# Mic_Circuit.net
KiCad netlist of a schematic drawn in Altium Designer
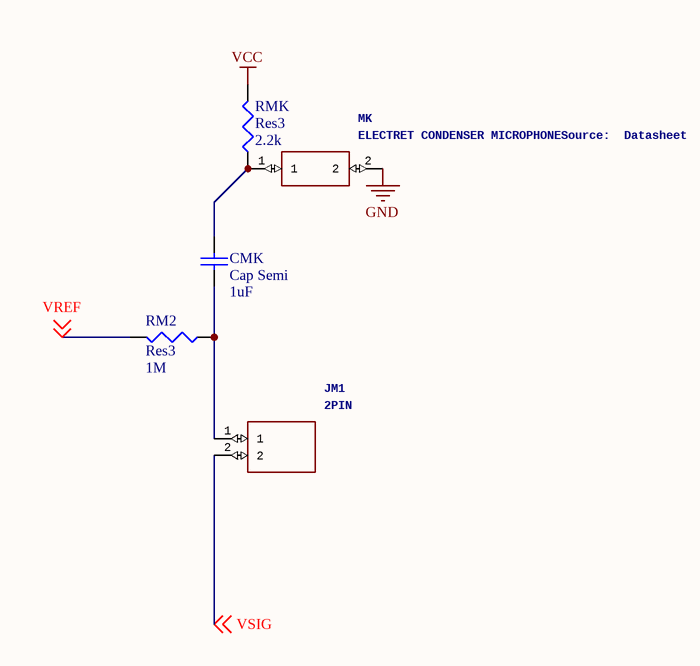
[diagram p0: Mic_Circuit.SchDoc]

(export (version "E")
  (design (tool "Eeschema 10.0.6"))
  (components
    (comp (ref "CMK")
      (value "Cap Semi")
      (footprint "1608[0603]")
      (description "Capacitor (Semiconductor SIM Model)")
      (fields (field (name "ALTIUM_VALUE") "1uF") (field (name "PUBLISHER") "Altium Limited"))
      (libsource (lib "Miscellaneous Devices") (part "Cap Semi"))
    )
    (comp (ref "JM1")
      (value "2PIN")
      (footprint "HDRV2W110P0X254_1X2_508X254X85")
      (fields
        (field (name "MANUFACTURER_PART_NUMBER") "61300211121")
        (field (name "RS_PART_NUMBER") "8281581P")
      )
      (libsource (lib "61300211121") (part "61300211121"))
    )
    (comp (ref "MK")
      (value "ELECTRET CONDENSER MICROPHONESource:  Datasheet")
      (footprint "CMA-4544PF-W")
      (fields (field (name "MANUFACTURER_PART_NUMBER") "CMA-4544PF-W"))
      (libsource (lib "CMA-4544PF-W") (part "CMA-4544PF-W"))
    )
    (comp (ref "RM2")
      (value "Res3")
      (footprint "1608[0603]")
      (description "Resistor")
      (fields (field (name "ALTIUM_VALUE") "1M") (field (name "PUBLISHER") "Altium Limited"))
      (libsource (lib "Miscellaneous Devices") (part "Res3"))
    )
    (comp (ref "RMK")
      (value "Res3")
      (footprint "1608[0603]")
      (description "Resistor")
      (fields (field (name "ALTIUM_VALUE") "2.2k") (field (name "PUBLISHER") "Altium Limited"))
      (libsource (lib "Miscellaneous Devices") (part "Res3"))
    )
  )
  (nets
    (net (code "1") (name "GND") (class "Default")
      (node (ref "MK") (pin "2") (pinfunction "2_2") (pintype "bidirectional"))
    )
    (net (code "2") (name "Net-(CMK-Pad1)") (class "Default")
      (node (ref "CMK") (pin "1") (pinfunction "1_1") (pintype "passive"))
      (node (ref "JM1") (pin "1") (pinfunction "1_1") (pintype "bidirectional"))
      (node (ref "RM2") (pin "2") (pinfunction "2_2") (pintype "passive"))
    )
    (net (code "3") (name "Net-(CMK-Pad2)") (class "Default")
      (node (ref "CMK") (pin "2") (pinfunction "2_2") (pintype "passive"))
      (node (ref "MK") (pin "1") (pinfunction "1_1") (pintype "bidirectional"))
      (node (ref "RMK") (pin "2") (pinfunction "2_2") (pintype "passive"))
    )
    (net (code "4") (name "VCC") (class "Default")
      (node (ref "RMK") (pin "1") (pinfunction "1_1") (pintype "passive"))
    )
    (net (code "5") (name "VREF") (class "Default")
      (node (ref "RM2") (pin "1") (pinfunction "1_1") (pintype "passive"))
    )
    (net (code "6") (name "VSIG") (class "Default")
      (node (ref "JM1") (pin "2") (pinfunction "2_2") (pintype "bidirectional"))
    )
  )
)
